# sensor.net
KiCad netlist of a schematic drawn in EAGLE
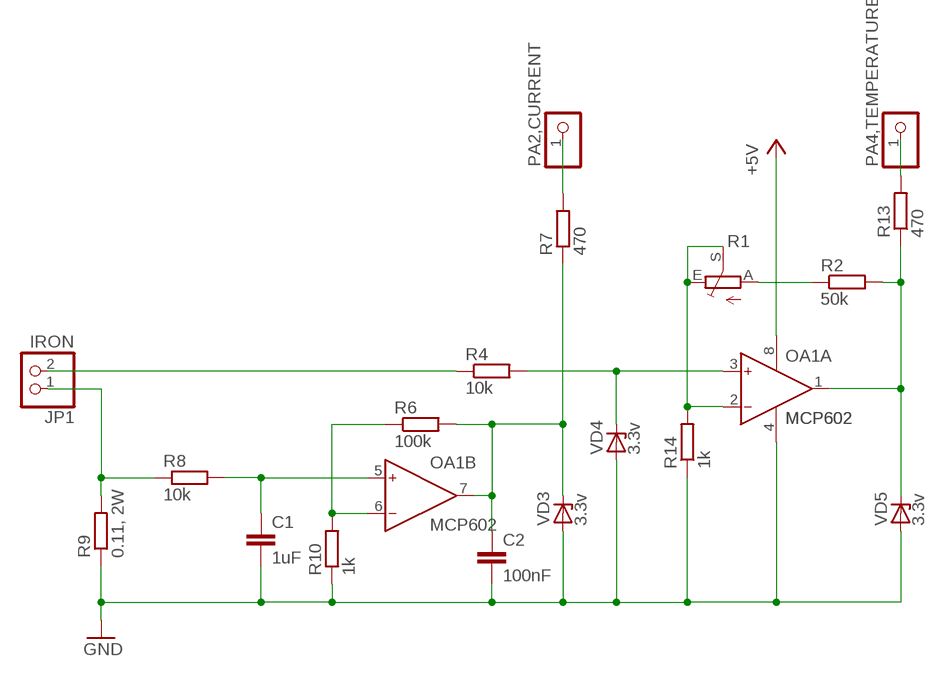
[diagram p0: schematic, sheet 1]

(export (version "E")
  (design (tool "Eeschema 10.0.6"))
  (components
    (comp (ref "C1")
      (value "1uF")
      (footprint "eagle-import:C025-024X044")
      (libsource (lib "eagle-import") (part "C-EU025-024X044"))
    )
    (comp (ref "C2")
      (value "100nF")
      (footprint "eagle-import:C025-024X044")
      (libsource (lib "eagle-import") (part "C-EU025-024X044"))
    )
    (comp (ref "JP1")
      (value "IRON")
      (footprint "eagle-import:1X02")
      (libsource (lib "eagle-import") (part "PINHD-1X2"))
    )
    (comp (ref "OA1")
      (value "MCP602")
      (footprint "eagle-import:DIL08")
      (libsource (lib "eagle-import") (part "AD822N"))
    )
    (comp (ref "PA2,CURRENT")
      (value "PINHD-1X1")
      (footprint "eagle-import:1X01")
      (libsource (lib "eagle-import") (part "PINHD-1X1"))
    )
    (comp (ref "PA4,TEMPERATURE")
      (value "PINHD-1X1")
      (footprint "eagle-import:1X01")
      (libsource (lib "eagle-import") (part "PINHD-1X1"))
    )
    (comp (ref "R1")
      (value "TRIM_EU-B64Y")
      (footprint "eagle-import:B64Y")
      (libsource (lib "eagle-import") (part "TRIM_EU-B64Y"))
    )
    (comp (ref "R2")
      (value "50k")
      (footprint "eagle-import:0204_5")
      (libsource (lib "eagle-import") (part "R-EU_0204/5"))
    )
    (comp (ref "R4")
      (value "10k")
      (footprint "eagle-import:0204_5")
      (libsource (lib "eagle-import") (part "R-EU_0204/5"))
    )
    (comp (ref "R6")
      (value "100k")
      (footprint "eagle-import:0204_5")
      (libsource (lib "eagle-import") (part "R-EU_0204/5"))
    )
    (comp (ref "R7")
      (value "470")
      (footprint "eagle-import:0204_5")
      (libsource (lib "eagle-import") (part "R-EU_0204/5"))
    )
    (comp (ref "R8")
      (value "10k")
      (footprint "eagle-import:0204_5")
      (libsource (lib "eagle-import") (part "R-EU_0204/5"))
    )
    (comp (ref "R9")
      (value "0.11, 2W")
      (footprint "eagle-import:0204_5")
      (libsource (lib "eagle-import") (part "R-EU_0204/5"))
    )
    (comp (ref "R10")
      (value "1k")
      (footprint "eagle-import:0204_5")
      (libsource (lib "eagle-import") (part "R-EU_0204/5"))
    )
    (comp (ref "R13")
      (value "470")
      (footprint "eagle-import:0204_5")
      (libsource (lib "eagle-import") (part "R-EU_0204/5"))
    )
    (comp (ref "R14")
      (value "1k")
      (footprint "eagle-import:0204_5")
      (libsource (lib "eagle-import") (part "R-EU_0204/5"))
    )
    (comp (ref "VD3")
      (value "3.3v")
      (footprint "eagle-import:C1702-15")
      (libsource (lib "eagle-import") (part "ZENER-DIODEC1702-15"))
    )
    (comp (ref "VD4")
      (value "3.3v")
      (footprint "eagle-import:C1702-15")
      (libsource (lib "eagle-import") (part "ZENER-DIODEC1702-15"))
    )
    (comp (ref "VD5")
      (value "3.3v")
      (footprint "eagle-import:C1702-15")
      (libsource (lib "eagle-import") (part "ZENER-DIODEC1702-15"))
    )
  )
  (nets
    (net (code "1") (name "+5V") (class "Default")
      (node (ref "OA1") (pin "8") (pinfunction "V+_8") (pintype "power_in"))
    )
    (net (code "2") (name "GND") (class "Default")
      (node (ref "C1") (pin "2") (pinfunction "2_2") (pintype "passive"))
      (node (ref "C2") (pin "2") (pinfunction "2_2") (pintype "passive"))
      (node (ref "OA1") (pin "4") (pinfunction "V-_4") (pintype "power_in"))
      (node (ref "R10") (pin "1") (pinfunction "1_1") (pintype "passive"))
      (node (ref "R14") (pin "1") (pinfunction "1_1") (pintype "passive"))
      (node (ref "R9") (pin "1") (pinfunction "1_1") (pintype "passive"))
      (node (ref "VD3") (pin "A") (pinfunction "A_A") (pintype "passive"))
      (node (ref "VD4") (pin "A") (pinfunction "A_A") (pintype "passive"))
      (node (ref "VD5") (pin "A") (pinfunction "A_A") (pintype "passive"))
    )
    (net (code "3") (name "Net-(JP1-Pad1)") (class "Default")
      (node (ref "JP1") (pin "1") (pinfunction "1_1") (pintype "passive"))
      (node (ref "R8") (pin "1") (pinfunction "1_1") (pintype "passive"))
      (node (ref "R9") (pin "2") (pinfunction "2_2") (pintype "passive"))
    )
    (net (code "4") (name "Net-(JP1-Pad2)") (class "Default")
      (node (ref "JP1") (pin "2") (pinfunction "2_2") (pintype "passive"))
      (node (ref "R4") (pin "1") (pinfunction "1_1") (pintype "passive"))
    )
    (net (code "5") (name "Net-(OA1A-IN+)") (class "Default")
      (node (ref "OA1") (pin "3") (pinfunction "IN+_3") (pintype "input"))
      (node (ref "R4") (pin "2") (pinfunction "2_2") (pintype "passive"))
      (node (ref "VD4") (pin "C") (pinfunction "C_C") (pintype "passive"))
    )
    (net (code "6") (name "Net-(OA1A-IN-)") (class "Default")
      (node (ref "OA1") (pin "2") (pinfunction "IN-_2") (pintype "input"))
      (node (ref "R1") (pin "E") (pinfunction "E_E") (pintype "passive"))
      (node (ref "R1") (pin "S") (pinfunction "S_S") (pintype "passive"))
      (node (ref "R14") (pin "2") (pinfunction "2_2") (pintype "passive"))
    )
    (net (code "7") (name "Net-(OA1A-OUT)") (class "Default")
      (node (ref "OA1") (pin "1") (pinfunction "OUT_1") (pintype "output"))
      (node (ref "R13") (pin "1") (pinfunction "1_1") (pintype "passive"))
      (node (ref "R2") (pin "2") (pinfunction "2_2") (pintype "passive"))
      (node (ref "VD5") (pin "C") (pinfunction "C_C") (pintype "passive"))
    )
    (net (code "8") (name "Net-(OA1B-IN+)") (class "Default")
      (node (ref "C1") (pin "1") (pinfunction "1_1") (pintype "passive"))
      (node (ref "OA1") (pin "5") (pinfunction "IN+_5") (pintype "input"))
      (node (ref "R8") (pin "2") (pinfunction "2_2") (pintype "passive"))
    )
    (net (code "9") (name "Net-(OA1B-IN-)") (class "Default")
      (node (ref "OA1") (pin "6") (pinfunction "IN-_6") (pintype "input"))
      (node (ref "R10") (pin "2") (pinfunction "2_2") (pintype "passive"))
      (node (ref "R6") (pin "1") (pinfunction "1_1") (pintype "passive"))
    )
    (net (code "10") (name "Net-(OA1B-OUT)") (class "Default")
      (node (ref "C2") (pin "1") (pinfunction "1_1") (pintype "passive"))
      (node (ref "OA1") (pin "7") (pinfunction "OUT_7") (pintype "output"))
      (node (ref "R6") (pin "2") (pinfunction "2_2") (pintype "passive"))
      (node (ref "R7") (pin "1") (pinfunction "1_1") (pintype "passive"))
      (node (ref "VD3") (pin "C") (pinfunction "C_C") (pintype "passive"))
    )
    (net (code "11") (name "Net-(PA2,CURRENT-Pad1)") (class "Default")
      (node (ref "PA2,CURRENT") (pin "1") (pinfunction "1_1") (pintype "passive"))
      (node (ref "R7") (pin "2") (pinfunction "2_2") (pintype "passive"))
    )
    (net (code "12") (name "Net-(PA4,TEMPERATURE-Pad1)") (class "Default")
      (node (ref "PA4,TEMPERATURE") (pin "1") (pinfunction "1_1") (pintype "passive"))
      (node (ref "R13") (pin "2") (pinfunction "2_2") (pintype "passive"))
    )
    (net (code "13") (name "Net-(R1-PadA)") (class "Default")
      (node (ref "R1") (pin "A") (pinfunction "A_A") (pintype "passive"))
      (node (ref "R2") (pin "1") (pinfunction "1_1") (pintype "passive"))
    )
  )
)
